# MICRO_SQUARED_SENSING_MCP1700_4.net
KiCad netlist of a schematic drawn in EAGLE
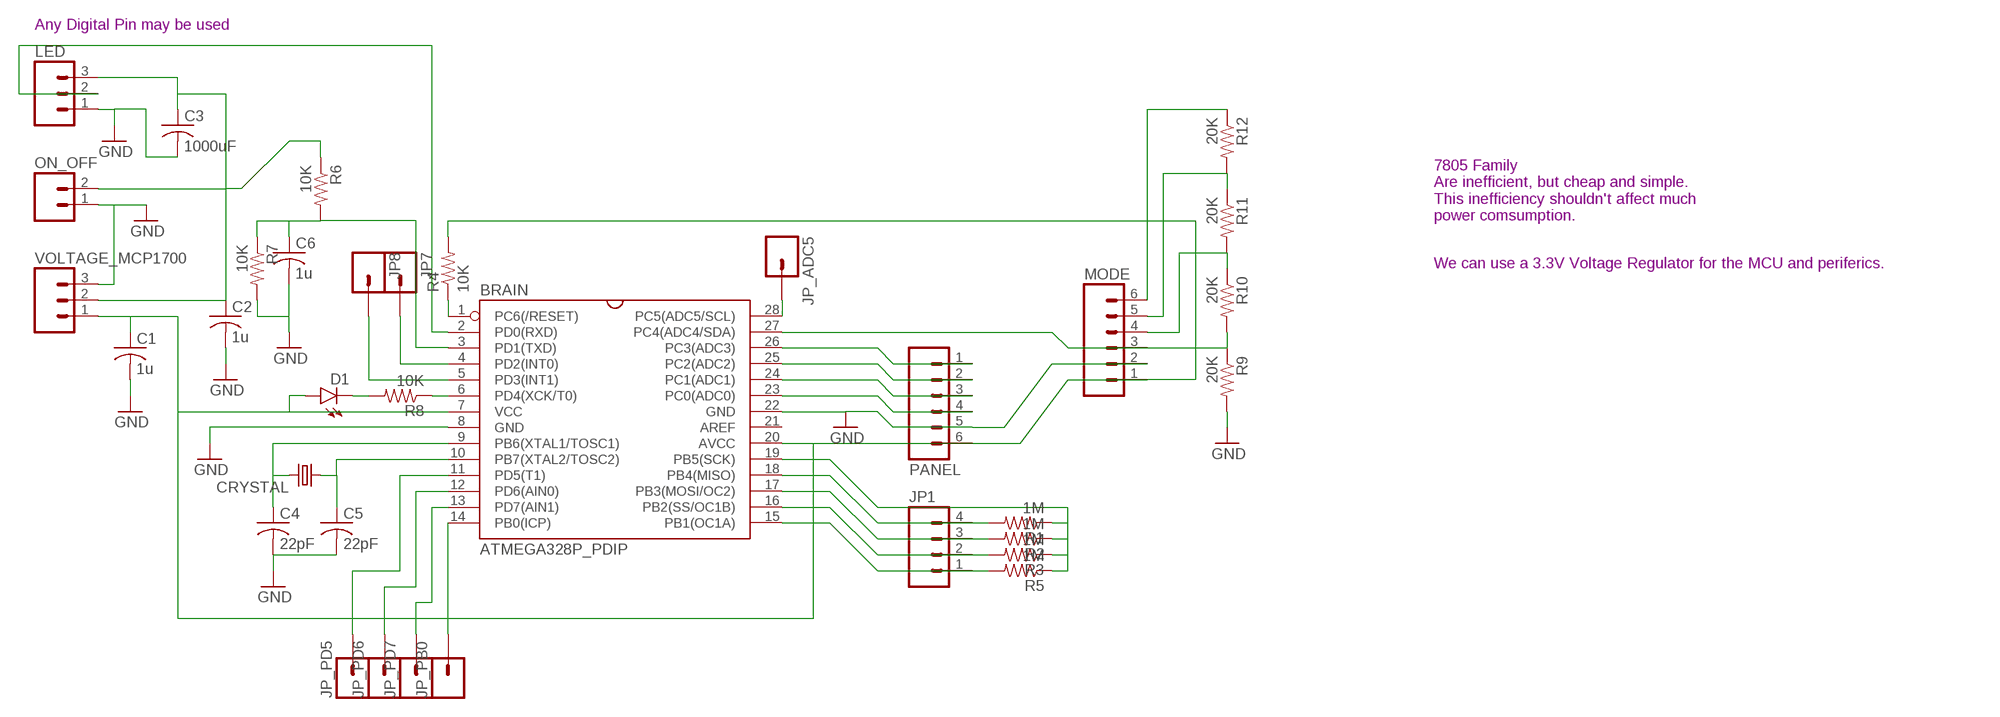
[diagram p0: schematic, sheet 1]

(export (version "E")
  (design (tool "Eeschema 10.0.6"))
  (components
    (comp (ref "BRAIN")
      (value "ATMEGA328P_PDIP")
      (footprint "eagle-import:DIL-28-3")
      (libsource (lib "eagle-import") (part "ATMEGA328P_PDIP"))
    )
    (comp (ref "C1")
      (value "1u")
      (footprint "eagle-import:C050-025X075")
      (libsource (lib "eagle-import") (part "C-US050-025X075"))
    )
    (comp (ref "C2")
      (value "1u")
      (footprint "eagle-import:C050-025X075")
      (libsource (lib "eagle-import") (part "C-US050-025X075"))
    )
    (comp (ref "C3")
      (value "1000uF")
      (footprint "eagle-import:C050-075X075")
      (libsource (lib "eagle-import") (part "C-US050-075X075"))
    )
    (comp (ref "C4")
      (value "22pF")
      (footprint "eagle-import:C025-024X044")
      (libsource (lib "eagle-import") (part "C-US025-024X044"))
    )
    (comp (ref "C5")
      (value "22pF")
      (footprint "eagle-import:C025-024X044")
      (libsource (lib "eagle-import") (part "C-US025-024X044"))
    )
    (comp (ref "C6")
      (value "1u")
      (footprint "eagle-import:C050-025X075")
      (libsource (lib "eagle-import") (part "C-US050-025X075"))
    )
    (comp (ref "CRYSTAL")
      (value "CRYSTALHC49US")
      (footprint "eagle-import:HC49US")
      (libsource (lib "eagle-import") (part "CRYSTALHC49US"))
    )
    (comp (ref "D1")
      (value "LED3MM")
      (footprint "eagle-import:LED3MM")
      (libsource (lib "eagle-import") (part "LED3MM"))
    )
    (comp (ref "JP1")
      (value "M04PTH")
      (footprint "eagle-import:1X04")
      (libsource (lib "eagle-import") (part "M04PTH"))
    )
    (comp (ref "JP7")
      (value "M01PTH")
      (footprint "eagle-import:1X01")
      (libsource (lib "eagle-import") (part "M01PTH"))
    )
    (comp (ref "JP8")
      (value "M01PTH")
      (footprint "eagle-import:1X01")
      (libsource (lib "eagle-import") (part "M01PTH"))
    )
    (comp (ref "JP_ADC5")
      (value "M01PTH")
      (footprint "eagle-import:1X01")
      (libsource (lib "eagle-import") (part "M01PTH"))
    )
    (comp (ref "JP_PB0")
      (value "M01PTH")
      (footprint "eagle-import:1X01")
      (libsource (lib "eagle-import") (part "M01PTH"))
    )
    (comp (ref "JP_PD5")
      (value "M01PTH")
      (footprint "eagle-import:1X01")
      (libsource (lib "eagle-import") (part "M01PTH"))
    )
    (comp (ref "JP_PD6")
      (value "M01PTH")
      (footprint "eagle-import:1X01")
      (libsource (lib "eagle-import") (part "M01PTH"))
    )
    (comp (ref "JP_PD7")
      (value "M01PTH")
      (footprint "eagle-import:1X01")
      (libsource (lib "eagle-import") (part "M01PTH"))
    )
    (comp (ref "LED")
      (value "M03PTH")
      (footprint "eagle-import:1X03")
      (libsource (lib "eagle-import") (part "M03PTH"))
    )
    (comp (ref "MODE")
      (value "M06SILK_FEMALE_PTH")
      (footprint "eagle-import:1X06")
      (libsource (lib "eagle-import") (part "M06SILK_FEMALE_PTH"))
    )
    (comp (ref "ON_OFF")
      (value "M02PTH")
      (footprint "eagle-import:1X02")
      (libsource (lib "eagle-import") (part "M02PTH"))
    )
    (comp (ref "PANEL")
      (value "M06NO_SILK_FEMALE_PTH")
      (footprint "eagle-import:1X06_NO_SILK")
      (libsource (lib "eagle-import") (part "M06NO_SILK_FEMALE_PTH"))
    )
    (comp (ref "R1")
      (value "1M")
      (footprint "eagle-import:AXIAL-0.3")
      (libsource (lib "eagle-import") (part "RESISTORAXIAL-0.3"))
    )
    (comp (ref "R2")
      (value "1M")
      (footprint "eagle-import:AXIAL-0.3")
      (libsource (lib "eagle-import") (part "RESISTORAXIAL-0.3"))
    )
    (comp (ref "R3")
      (value "1M")
      (footprint "eagle-import:AXIAL-0.3")
      (libsource (lib "eagle-import") (part "RESISTORAXIAL-0.3"))
    )
    (comp (ref "R4")
      (value "10K")
      (footprint "eagle-import:AXIAL-0.3")
      (libsource (lib "eagle-import") (part "RESISTORAXIAL-0.3"))
    )
    (comp (ref "R5")
      (value "1M")
      (footprint "eagle-import:AXIAL-0.3")
      (libsource (lib "eagle-import") (part "RESISTORAXIAL-0.3"))
    )
    (comp (ref "R6")
      (value "10K")
      (footprint "eagle-import:AXIAL-0.3")
      (libsource (lib "eagle-import") (part "RESISTORAXIAL-0.3"))
    )
    (comp (ref "R7")
      (value "10K")
      (footprint "eagle-import:AXIAL-0.3")
      (libsource (lib "eagle-import") (part "RESISTORAXIAL-0.3"))
    )
    (comp (ref "R8")
      (value "10K")
      (footprint "eagle-import:AXIAL-0.3")
      (libsource (lib "eagle-import") (part "RESISTORAXIAL-0.3"))
    )
    (comp (ref "R9")
      (value "20K")
      (footprint "eagle-import:AXIAL-0.3")
      (libsource (lib "eagle-import") (part "RESISTORAXIAL-0.3"))
    )
    (comp (ref "R10")
      (value "20K")
      (footprint "eagle-import:AXIAL-0.3")
      (libsource (lib "eagle-import") (part "RESISTORAXIAL-0.3"))
    )
    (comp (ref "R11")
      (value "20K")
      (footprint "eagle-import:AXIAL-0.3")
      (libsource (lib "eagle-import") (part "RESISTORAXIAL-0.3"))
    )
    (comp (ref "R12")
      (value "20K")
      (footprint "eagle-import:AXIAL-0.3")
      (libsource (lib "eagle-import") (part "RESISTORAXIAL-0.3"))
    )
    (comp (ref "VOLTAGE_MCP1700")
      (value "M03PTH")
      (footprint "eagle-import:1X03")
      (libsource (lib "eagle-import") (part "M03PTH"))
    )
  )
  (nets
    (net (code "1") (name "GND") (class "Default")
      (node (ref "BRAIN") (pin "22") (pinfunction "GND_22") (pintype "bidirectional"))
      (node (ref "BRAIN") (pin "8") (pinfunction "GND_8") (pintype "bidirectional"))
      (node (ref "C1") (pin "2") (pinfunction "2_2") (pintype "passive"))
      (node (ref "C2") (pin "2") (pinfunction "2_2") (pintype "passive"))
      (node (ref "C3") (pin "2") (pinfunction "2_2") (pintype "passive"))
      (node (ref "C4") (pin "2") (pinfunction "2_2") (pintype "passive"))
      (node (ref "C5") (pin "2") (pinfunction "2_2") (pintype "passive"))
      (node (ref "C6") (pin "2") (pinfunction "2_2") (pintype "passive"))
      (node (ref "LED") (pin "1") (pinfunction "1_1") (pintype "passive"))
      (node (ref "MODE") (pin "2") (pinfunction "2_2") (pintype "passive"))
      (node (ref "ON_OFF") (pin "1") (pinfunction "1_1") (pintype "passive"))
      (node (ref "PANEL") (pin "5") (pinfunction "5_5") (pintype "passive"))
      (node (ref "R7") (pin "P$2") (pinfunction "2_P$2") (pintype "passive"))
      (node (ref "R9") (pin "P$2") (pinfunction "2_P$2") (pintype "passive"))
      (node (ref "VOLTAGE_MCP1700") (pin "3") (pinfunction "3_3") (pintype "passive"))
    )
    (net (code "2") (name "Net-(BRAIN-AVCC)") (class "Default")
      (node (ref "BRAIN") (pin "20") (pinfunction "AVCC_20") (pintype "bidirectional"))
      (node (ref "BRAIN") (pin "7") (pinfunction "VCC_7") (pintype "bidirectional"))
      (node (ref "C1") (pin "1") (pinfunction "1_1") (pintype "passive"))
      (node (ref "D1") (pin "A") (pinfunction "A_A") (pintype "passive"))
      (node (ref "MODE") (pin "1") (pinfunction "1_1") (pintype "passive"))
      (node (ref "PANEL") (pin "6") (pinfunction "6_6") (pintype "passive"))
      (node (ref "R4") (pin "P$2") (pinfunction "2_P$2") (pintype "passive"))
      (node (ref "VOLTAGE_MCP1700") (pin "1") (pinfunction "1_1") (pintype "passive"))
    )
    (net (code "3") (name "Net-(BRAIN-PB0(ICP))") (class "Default")
      (node (ref "BRAIN") (pin "14") (pinfunction "PB0(ICP)_14") (pintype "bidirectional"))
      (node (ref "JP_PB0") (pin "1") (pinfunction "1_1") (pintype "passive"))
    )
    (net (code "4") (name "Net-(BRAIN-PB1(OC1A))") (class "Default")
      (node (ref "BRAIN") (pin "15") (pinfunction "PB1(OC1A)_15") (pintype "bidirectional"))
      (node (ref "JP1") (pin "1") (pinfunction "1_1") (pintype "passive"))
      (node (ref "R5") (pin "P$2") (pinfunction "2_P$2") (pintype "passive"))
    )
    (net (code "5") (name "Net-(BRAIN-PB2(SS{slash}OC1B))") (class "Default")
      (node (ref "BRAIN") (pin "16") (pinfunction "PB2(SS/OC1B)_16") (pintype "bidirectional"))
      (node (ref "JP1") (pin "2") (pinfunction "2_2") (pintype "passive"))
      (node (ref "R3") (pin "P$2") (pinfunction "2_P$2") (pintype "passive"))
    )
    (net (code "6") (name "Net-(BRAIN-PB3(MOSI{slash}OC2))") (class "Default")
      (node (ref "BRAIN") (pin "17") (pinfunction "PB3(MOSI/OC2)_17") (pintype "bidirectional"))
      (node (ref "JP1") (pin "3") (pinfunction "3_3") (pintype "passive"))
      (node (ref "R2") (pin "P$2") (pinfunction "2_P$2") (pintype "passive"))
    )
    (net (code "7") (name "Net-(BRAIN-PB4(MISO))") (class "Default")
      (node (ref "BRAIN") (pin "18") (pinfunction "PB4(MISO)_18") (pintype "bidirectional"))
      (node (ref "JP1") (pin "4") (pinfunction "4_4") (pintype "passive"))
      (node (ref "R1") (pin "P$2") (pinfunction "2_P$2") (pintype "passive"))
    )
    (net (code "8") (name "Net-(BRAIN-PB5(SCK))") (class "Default")
      (node (ref "BRAIN") (pin "19") (pinfunction "PB5(SCK)_19") (pintype "bidirectional"))
      (node (ref "R1") (pin "P$1") (pinfunction "1_P$1") (pintype "passive"))
      (node (ref "R2") (pin "P$1") (pinfunction "1_P$1") (pintype "passive"))
      (node (ref "R3") (pin "P$1") (pinfunction "1_P$1") (pintype "passive"))
      (node (ref "R5") (pin "P$1") (pinfunction "1_P$1") (pintype "passive"))
    )
    (net (code "9") (name "Net-(BRAIN-PB6(XTAL1{slash}TOSC1))") (class "Default")
      (node (ref "BRAIN") (pin "9") (pinfunction "PB6(XTAL1/TOSC1)_9") (pintype "bidirectional"))
      (node (ref "C4") (pin "1") (pinfunction "1_1") (pintype "passive"))
      (node (ref "CRYSTAL") (pin "2") (pinfunction "2_2") (pintype "passive"))
    )
    (net (code "10") (name "Net-(BRAIN-PB7(XTAL2{slash}TOSC2))") (class "Default")
      (node (ref "BRAIN") (pin "10") (pinfunction "PB7(XTAL2/TOSC2)_10") (pintype "bidirectional"))
      (node (ref "C5") (pin "1") (pinfunction "1_1") (pintype "passive"))
      (node (ref "CRYSTAL") (pin "1") (pinfunction "1_1") (pintype "passive"))
    )
    (net (code "11") (name "Net-(BRAIN-PC0(ADC0))") (class "Default")
      (node (ref "BRAIN") (pin "23") (pinfunction "PC0(ADC0)_23") (pintype "bidirectional"))
      (node (ref "PANEL") (pin "4") (pinfunction "4_4") (pintype "passive"))
    )
    (net (code "12") (name "Net-(BRAIN-PC1(ADC1))") (class "Default")
      (node (ref "BRAIN") (pin "24") (pinfunction "PC1(ADC1)_24") (pintype "bidirectional"))
      (node (ref "PANEL") (pin "3") (pinfunction "3_3") (pintype "passive"))
    )
    (net (code "13") (name "Net-(BRAIN-PC2(ADC2))") (class "Default")
      (node (ref "BRAIN") (pin "25") (pinfunction "PC2(ADC2)_25") (pintype "bidirectional"))
      (node (ref "PANEL") (pin "2") (pinfunction "2_2") (pintype "passive"))
    )
    (net (code "14") (name "Net-(BRAIN-PC3(ADC3))") (class "Default")
      (node (ref "BRAIN") (pin "26") (pinfunction "PC3(ADC3)_26") (pintype "bidirectional"))
      (node (ref "PANEL") (pin "1") (pinfunction "1_1") (pintype "passive"))
    )
    (net (code "15") (name "Net-(BRAIN-PC4(ADC4{slash}SDA))") (class "Default")
      (node (ref "BRAIN") (pin "27") (pinfunction "PC4(ADC4/SDA)_27") (pintype "bidirectional"))
      (node (ref "MODE") (pin "3") (pinfunction "3_3") (pintype "passive"))
      (node (ref "R10") (pin "P$2") (pinfunction "2_P$2") (pintype "passive"))
      (node (ref "R9") (pin "P$1") (pinfunction "1_P$1") (pintype "passive"))
    )
    (net (code "16") (name "Net-(BRAIN-PC5(ADC5{slash}SCL))") (class "Default")
      (node (ref "BRAIN") (pin "28") (pinfunction "PC5(ADC5/SCL)_28") (pintype "bidirectional"))
      (node (ref "JP_ADC5") (pin "1") (pinfunction "1_1") (pintype "passive"))
    )
    (net (code "17") (name "Net-(BRAIN-PC6({slash}RESET))") (class "Default")
      (node (ref "BRAIN") (pin "1") (pinfunction "PC6(/RESET)_1") (pintype "bidirectional"))
      (node (ref "R4") (pin "P$1") (pinfunction "1_P$1") (pintype "passive"))
    )
    (net (code "18") (name "Net-(BRAIN-PD0(RXD))") (class "Default")
      (node (ref "BRAIN") (pin "2") (pinfunction "PD0(RXD)_2") (pintype "bidirectional"))
      (node (ref "LED") (pin "2") (pinfunction "2_2") (pintype "passive"))
    )
    (net (code "19") (name "Net-(BRAIN-PD1(TXD))") (class "Default")
      (node (ref "BRAIN") (pin "3") (pinfunction "PD1(TXD)_3") (pintype "bidirectional"))
      (node (ref "C6") (pin "1") (pinfunction "1_1") (pintype "passive"))
      (node (ref "R6") (pin "P$2") (pinfunction "2_P$2") (pintype "passive"))
      (node (ref "R7") (pin "P$1") (pinfunction "1_P$1") (pintype "passive"))
    )
    (net (code "20") (name "Net-(BRAIN-PD2(INT0))") (class "Default")
      (node (ref "BRAIN") (pin "4") (pinfunction "PD2(INT0)_4") (pintype "bidirectional"))
      (node (ref "JP7") (pin "1") (pinfunction "1_1") (pintype "passive"))
    )
    (net (code "21") (name "Net-(BRAIN-PD3(INT1))") (class "Default")
      (node (ref "BRAIN") (pin "5") (pinfunction "PD3(INT1)_5") (pintype "bidirectional"))
      (node (ref "JP8") (pin "1") (pinfunction "1_1") (pintype "passive"))
    )
    (net (code "22") (name "Net-(BRAIN-PD4(XCK{slash}T0))") (class "Default")
      (node (ref "BRAIN") (pin "6") (pinfunction "PD4(XCK/T0)_6") (pintype "bidirectional"))
      (node (ref "R8") (pin "P$1") (pinfunction "1_P$1") (pintype "passive"))
    )
    (net (code "23") (name "Net-(BRAIN-PD5(T1))") (class "Default")
      (node (ref "BRAIN") (pin "11") (pinfunction "PD5(T1)_11") (pintype "bidirectional"))
      (node (ref "JP_PD5") (pin "1") (pinfunction "1_1") (pintype "passive"))
    )
    (net (code "24") (name "Net-(BRAIN-PD6(AIN0))") (class "Default")
      (node (ref "BRAIN") (pin "12") (pinfunction "PD6(AIN0)_12") (pintype "bidirectional"))
      (node (ref "JP_PD6") (pin "1") (pinfunction "1_1") (pintype "passive"))
    )
    (net (code "25") (name "Net-(BRAIN-PD7(AIN1))") (class "Default")
      (node (ref "BRAIN") (pin "13") (pinfunction "PD7(AIN1)_13") (pintype "bidirectional"))
      (node (ref "JP_PD7") (pin "1") (pinfunction "1_1") (pintype "passive"))
    )
    (net (code "26") (name "Net-(D1-C)") (class "Default")
      (node (ref "D1") (pin "K") (pinfunction "C_K") (pintype "passive"))
      (node (ref "R8") (pin "P$2") (pinfunction "2_P$2") (pintype "passive"))
    )
    (net (code "27") (name "Net-(R6-1)") (class "Default")
      (node (ref "C2") (pin "1") (pinfunction "1_1") (pintype "passive"))
      (node (ref "C3") (pin "1") (pinfunction "1_1") (pintype "passive"))
      (node (ref "LED") (pin "3") (pinfunction "3_3") (pintype "passive"))
      (node (ref "ON_OFF") (pin "2") (pinfunction "2_2") (pintype "passive"))
      (node (ref "R6") (pin "P$1") (pinfunction "1_P$1") (pintype "passive"))
      (node (ref "VOLTAGE_MCP1700") (pin "2") (pinfunction "2_2") (pintype "passive"))
    )
    (net (code "28") (name "Net-(R10-1)") (class "Default")
      (node (ref "MODE") (pin "4") (pinfunction "4_4") (pintype "passive"))
      (node (ref "R10") (pin "P$1") (pinfunction "1_P$1") (pintype "passive"))
      (node (ref "R11") (pin "P$2") (pinfunction "2_P$2") (pintype "passive"))
    )
    (net (code "29") (name "Net-(R11-1)") (class "Default")
      (node (ref "MODE") (pin "5") (pinfunction "5_5") (pintype "passive"))
      (node (ref "R11") (pin "P$1") (pinfunction "1_P$1") (pintype "passive"))
      (node (ref "R12") (pin "P$2") (pinfunction "2_P$2") (pintype "passive"))
    )
    (net (code "30") (name "Net-(R12-1)") (class "Default")
      (node (ref "MODE") (pin "6") (pinfunction "6_6") (pintype "passive"))
      (node (ref "R12") (pin "P$1") (pinfunction "1_P$1") (pintype "passive"))
    )
    (net (code "31") (name "unconnected-(BRAIN-AREF-Pad21)") (class "Default")
      (node (ref "BRAIN") (pin "21") (pinfunction "AREF_21") (pintype "bidirectional"))
    )
  )
)
